# Esquematico_DIY_2.net
KiCad netlist of a schematic drawn in Altium Designer
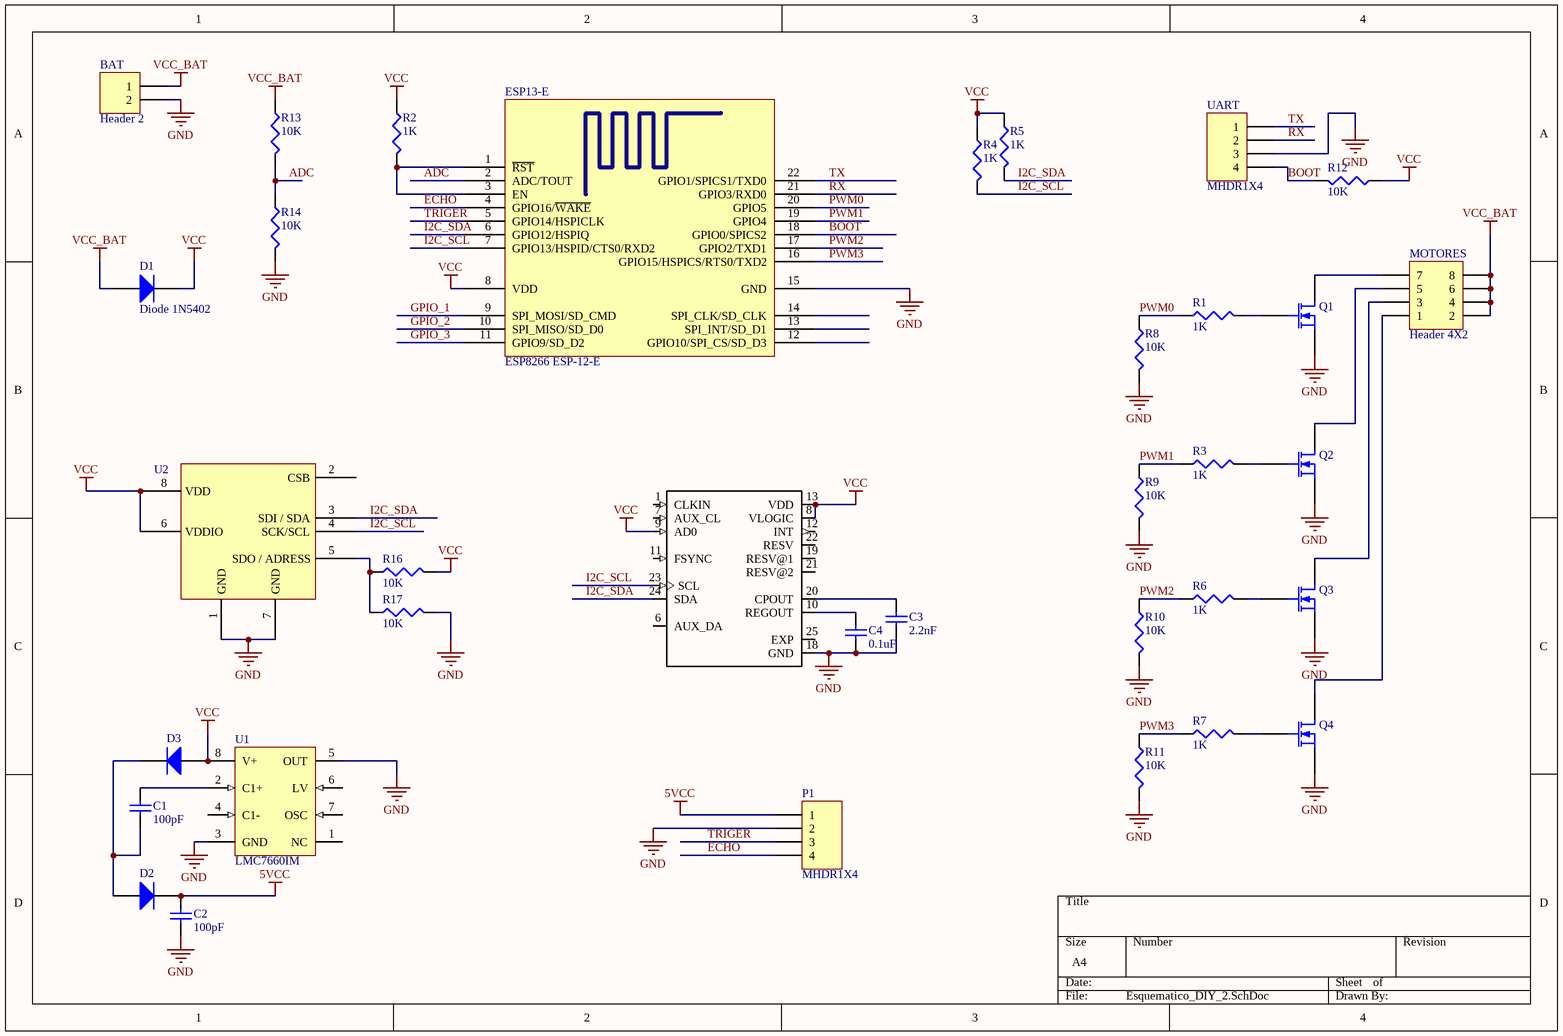
[diagram p0: Esquematico_DIY_2.SchDoc]

(export (version "E")
  (design (tool "Eeschema 10.0.6"))
  (components
    (comp (ref "BAT")
      (value "Header 2")
      (footprint "Miscellaneous Connectors:MHDR1X2")
      (description "Header, 2-Pin")
      (fields (field (name "PUBLISHER") "Altium Limited"))
      (libsource (lib "Miscellaneous Connectors") (part "Header 2"))
    )
    (comp (ref "C1")
      (value "100pF")
      (footprint "Miscellaneous Devices:C0805")
      (description "Capacitor")
      (fields (field (name "Comment") "Cap") (field (name "PUBLISHER") "Altium Limited"))
      (libsource (lib "Miscellaneous Devices") (part "Cap"))
    )
    (comp (ref "C2")
      (value "100pF")
      (footprint "Miscellaneous Devices:C0805")
      (description "Capacitor")
      (fields (field (name "Comment") "Cap") (field (name "PUBLISHER") "Altium Limited"))
      (libsource (lib "Miscellaneous Devices") (part "Cap"))
    )
    (comp (ref "C3")
      (value "2.2nF")
      (footprint "Miscellaneous Devices:C0805")
      (description "Capacitor")
      (fields (field (name "Comment") "Cap") (field (name "PUBLISHER") "Altium Limited"))
      (libsource (lib "Miscellaneous Devices") (part "Cap"))
    )
    (comp (ref "C4")
      (value "0.1uF")
      (footprint "Miscellaneous Devices:C0805")
      (description "Capacitor")
      (fields (field (name "Comment") "Cap") (field (name "PUBLISHER") "Altium Limited"))
      (libsource (lib "Miscellaneous Devices") (part "Cap"))
    )
    (comp (ref "D1")
      (value "Diode 1N5402")
      (footprint "DSO-C2/X2.3")
      (description "3 Amp General Purpose Rectifier")
      (fields (field (name "PUBLISHER") "Altium Limited"))
      (libsource (lib "Miscellaneous Devices") (part "Diode 1N5402"))
    )
    (comp (ref "D2")
      (value "Diode 1N5402")
      (footprint "DSO-C2/Z6.7")
      (description "3 Amp General Purpose Rectifier")
      (fields (field (name "PUBLISHER") "Altium Limited"))
      (libsource (lib "Miscellaneous Devices") (part "Diode 1N5402"))
    )
    (comp (ref "D3")
      (value "Diode 1N5402")
      (footprint "DSO-C2/Z6.7")
      (description "3 Amp General Purpose Rectifier")
      (fields (field (name "PUBLISHER") "Altium Limited"))
      (libsource (lib "Miscellaneous Devices") (part "Diode 1N5402"))
    )
    (comp (ref "ESP13-E")
      (value "ESP8266 ESP-12-E")
      (footprint "ESP8266:ESP8266 ESP-12-E B")
      (libsource (lib "ESP8266") (part "ESP8266 ESP-12-E"))
    )
    (comp (ref "MOTORES")
      (value "Header 4X2")
      (footprint "HDR2X4")
      (description "Header, 4-Pin, Dual row")
      (fields (field (name "PUBLISHER") "Altium Limited"))
      (libsource (lib "Miscellaneous Connectors") (part "Header 4X2"))
    )
    (comp (ref "P1")
      (value "MHDR1X4")
      (footprint "MHDR1X4")
      (description "Header, 4-Pin")
      (fields (field (name "PUBLISHER") "Altium Limited"))
      (libsource (lib "") (part "MHDR1X4_1"))
    )
    (comp (ref "Q1")
      (value "MOSFET-N")
      (footprint "PBL - SMD Packages:SOT23-3")
      (description "N-Channel MOSFET")
      (fields (field (name "PUBLISHER") "Altium Limited"))
      (libsource (lib "Miscellaneous Devices") (part "MOSFET-N"))
    )
    (comp (ref "Q2")
      (value "MOSFET-N")
      (footprint "PBL - SMD Packages:SOT23-3")
      (description "N-Channel MOSFET")
      (fields (field (name "PUBLISHER") "Altium Limited"))
      (libsource (lib "Miscellaneous Devices") (part "MOSFET-N"))
    )
    (comp (ref "Q3")
      (value "MOSFET-N")
      (footprint "PBL - SMD Packages:SOT23-3")
      (description "N-Channel MOSFET")
      (fields (field (name "PUBLISHER") "Altium Limited"))
      (libsource (lib "Miscellaneous Devices") (part "MOSFET-N"))
    )
    (comp (ref "Q4")
      (value "MOSFET-N")
      (footprint "PBL - SMD Packages:SOT23-3")
      (description "N-Channel MOSFET")
      (fields (field (name "PUBLISHER") "Altium Limited"))
      (libsource (lib "Miscellaneous Devices") (part "MOSFET-N"))
    )
    (comp (ref "R1")
      (value "1K")
      (footprint "C0805")
      (description "Resistor")
      (fields (field (name "Comment") "Res3") (field (name "PUBLISHER") "Altium Limited"))
      (libsource (lib "Miscellaneous Devices") (part "Res3"))
    )
    (comp (ref "R2")
      (value "1K")
      (footprint "C0805")
      (description "Resistor")
      (fields (field (name "Comment") "Res3") (field (name "PUBLISHER") "Altium Limited"))
      (libsource (lib "Miscellaneous Devices") (part "Res3"))
    )
    (comp (ref "R3")
      (value "1K")
      (footprint "C0805")
      (description "Resistor")
      (fields (field (name "Comment") "Res3") (field (name "PUBLISHER") "Altium Limited"))
      (libsource (lib "Miscellaneous Devices") (part "Res3"))
    )
    (comp (ref "R4")
      (value "1K")
      (footprint "C1206")
      (description "Resistor")
      (fields (field (name "Comment") "Res3") (field (name "PUBLISHER") "Altium Limited"))
      (libsource (lib "Miscellaneous Devices") (part "Res3"))
    )
    (comp (ref "R5")
      (value "1K")
      (footprint "C1206")
      (description "Resistor")
      (fields (field (name "Comment") "Res3") (field (name "PUBLISHER") "Altium Limited"))
      (libsource (lib "Miscellaneous Devices") (part "Res3"))
    )
    (comp (ref "R6")
      (value "1K")
      (footprint "C0805")
      (description "Resistor")
      (fields (field (name "Comment") "Res3") (field (name "PUBLISHER") "Altium Limited"))
      (libsource (lib "Miscellaneous Devices") (part "Res3"))
    )
    (comp (ref "R7")
      (value "1K")
      (footprint "C0805")
      (description "Resistor")
      (fields (field (name "Comment") "Res3") (field (name "PUBLISHER") "Altium Limited"))
      (libsource (lib "Miscellaneous Devices") (part "Res3"))
    )
    (comp (ref "R8")
      (value "10K")
      (footprint "C0805")
      (description "Resistor")
      (fields (field (name "Comment") "Res3") (field (name "PUBLISHER") "Altium Limited"))
      (libsource (lib "Miscellaneous Devices") (part "Res3"))
    )
    (comp (ref "R9")
      (value "10K")
      (footprint "C0805")
      (description "Resistor")
      (fields (field (name "Comment") "Res3") (field (name "PUBLISHER") "Altium Limited"))
      (libsource (lib "Miscellaneous Devices") (part "Res3"))
    )
    (comp (ref "R10")
      (value "10K")
      (footprint "C0805")
      (description "Resistor")
      (fields (field (name "Comment") "Res3") (field (name "PUBLISHER") "Altium Limited"))
      (libsource (lib "Miscellaneous Devices") (part "Res3"))
    )
    (comp (ref "R11")
      (value "10K")
      (footprint "C0805")
      (description "Resistor")
      (fields (field (name "Comment") "Res3") (field (name "PUBLISHER") "Altium Limited"))
      (libsource (lib "Miscellaneous Devices") (part "Res3"))
    )
    (comp (ref "R12")
      (value "10K")
      (footprint "C0805")
      (description "Resistor")
      (fields (field (name "Comment") "Res3") (field (name "PUBLISHER") "Altium Limited"))
      (libsource (lib "Miscellaneous Devices") (part "Res3"))
    )
    (comp (ref "R13")
      (value "10K")
      (footprint "C0805")
      (description "Resistor")
      (fields (field (name "Comment") "Res3") (field (name "PUBLISHER") "Altium Limited"))
      (libsource (lib "Miscellaneous Devices") (part "Res3"))
    )
    (comp (ref "R14")
      (value "10K")
      (footprint "C0805")
      (description "Resistor")
      (fields (field (name "Comment") "Res3") (field (name "PUBLISHER") "Altium Limited"))
      (libsource (lib "Miscellaneous Devices") (part "Res3"))
    )
    (comp (ref "R16")
      (value "10K")
      (footprint "C0805")
      (description "Resistor")
      (fields (field (name "Comment") "Res3") (field (name "PUBLISHER") "Altium Limited"))
      (libsource (lib "Miscellaneous Devices") (part "Res3"))
    )
    (comp (ref "R17")
      (value "10K")
      (footprint "C1206")
      (description "Resistor")
      (fields (field (name "Comment") "Res3") (field (name "PUBLISHER") "Altium Limited"))
      (libsource (lib "Miscellaneous Devices") (part "Res3"))
    )
    (comp (ref "U1")
      (value "LMC7660IM")
      (footprint "M08A_N")
      (description "Switched Capacitor Voltage Converter, 8-pin Narrow SOIC")
      (fields
        (field (name "MANUFACTURER") "National Semiconductor")
        (field (name "PUBLISHER") "Altium Limited")
      )
      (libsource (lib "NSC Switch Caps") (part "LMC7660IM"))
    )
    (comp (ref "U2")
      (value "BMP280")
      (footprint "LGA-8_BMP280(Primary)")
      (description "Barometro")
      (libsource (lib "BMP280") (part "BMP280"))
    )
    (comp (ref "U3")
      (value "MPU-6050")
      (footprint "QFN50P400X400X95-25N")
      (libsource (lib "MPU-6050") (part "MPU-6050"))
    )
    (comp (ref "UART")
      (value "MHDR1X4")
      (footprint "MHDR1X4")
      (description "Header, 4-Pin")
      (fields (field (name "PUBLISHER") "Altium Limited"))
      (libsource (lib "Miscellaneous Connectors") (part "MHDR1X4"))
    )
  )
  (nets
    (net (code "1") (name "/ADC") (class "Default")
      (node (ref "ESP13-E") (pin "2") (pinfunction "ADC/TOUT_2") (pintype "passive"))
      (node (ref "R13") (pin "2") (pinfunction "2_2") (pintype "passive"))
      (node (ref "R14") (pin "1") (pinfunction "1_1") (pintype "passive"))
    )
    (net (code "2") (name "/BOOT") (class "Default")
      (node (ref "ESP13-E") (pin "18") (pinfunction "GPIO0/SPICS2_18") (pintype "passive"))
      (node (ref "R12") (pin "2") (pinfunction "2_2") (pintype "passive"))
      (node (ref "UART") (pin "4") (pinfunction "4_4") (pintype "passive"))
    )
    (net (code "3") (name "/ECHO") (class "Default")
      (node (ref "ESP13-E") (pin "4") (pinfunction "GPIO16/~{WAKE}_4") (pintype "passive"))
      (node (ref "P1") (pin "4") (pinfunction "4_4") (pintype "passive"))
    )
    (net (code "4") (name "/GPIO_1") (class "Default")
      (node (ref "ESP13-E") (pin "9") (pinfunction "SPI_MOSI/SD_CMD_9") (pintype "passive"))
    )
    (net (code "5") (name "/GPIO_2") (class "Default")
      (node (ref "ESP13-E") (pin "10") (pinfunction "SPI_MISO/SD_D0_10") (pintype "passive"))
    )
    (net (code "6") (name "/GPIO_3") (class "Default")
      (node (ref "ESP13-E") (pin "11") (pinfunction "GPIO9/SD_D2_11") (pintype "passive"))
    )
    (net (code "7") (name "/I2C_SCL") (class "Default")
      (node (ref "ESP13-E") (pin "7") (pinfunction "GPIO13/HSPID/CTS0/RXD2_7") (pintype "passive"))
      (node (ref "R4") (pin "1") (pinfunction "1_1") (pintype "passive"))
      (node (ref "U2") (pin "4") (pinfunction "SCK/SCL_4") (pintype "passive"))
      (node (ref "U3") (pin "23") (pinfunction "SCL_23") (pintype "input"))
    )
    (net (code "8") (name "/I2C_SDA") (class "Default")
      (node (ref "ESP13-E") (pin "6") (pinfunction "GPIO12/HSPIQ_6") (pintype "passive"))
      (node (ref "R5") (pin "1") (pinfunction "1_1") (pintype "passive"))
      (node (ref "U2") (pin "3") (pinfunction "SDI_/_SDA_3") (pintype "passive"))
      (node (ref "U3") (pin "24") (pinfunction "SDA_24") (pintype "bidirectional"))
    )
    (net (code "9") (name "/PWM0") (class "Default")
      (node (ref "ESP13-E") (pin "20") (pinfunction "GPIO5_20") (pintype "passive"))
      (node (ref "R1") (pin "1") (pinfunction "1_1") (pintype "passive"))
      (node (ref "R8") (pin "1") (pinfunction "1_1") (pintype "passive"))
    )
    (net (code "10") (name "/PWM1") (class "Default")
      (node (ref "ESP13-E") (pin "19") (pinfunction "GPIO4_19") (pintype "passive"))
      (node (ref "R3") (pin "1") (pinfunction "1_1") (pintype "passive"))
      (node (ref "R9") (pin "1") (pinfunction "1_1") (pintype "passive"))
    )
    (net (code "11") (name "/PWM2") (class "Default")
      (node (ref "ESP13-E") (pin "17") (pinfunction "GPIO2/TXD1_17") (pintype "passive"))
      (node (ref "R10") (pin "1") (pinfunction "1_1") (pintype "passive"))
      (node (ref "R6") (pin "1") (pinfunction "1_1") (pintype "passive"))
    )
    (net (code "12") (name "/PWM3") (class "Default")
      (node (ref "ESP13-E") (pin "16") (pinfunction "GPIO15/HSPICS/RTS0/TXD2_16") (pintype "passive"))
      (node (ref "R11") (pin "1") (pinfunction "1_1") (pintype "passive"))
      (node (ref "R7") (pin "1") (pinfunction "1_1") (pintype "passive"))
    )
    (net (code "13") (name "/RX") (class "Default")
      (node (ref "ESP13-E") (pin "21") (pinfunction "GPIO3/RXD0_21") (pintype "passive"))
      (node (ref "UART") (pin "2") (pinfunction "2_2") (pintype "passive"))
    )
    (net (code "14") (name "/TRIGER") (class "Default")
      (node (ref "ESP13-E") (pin "5") (pinfunction "GPIO14/HSPICLK_5") (pintype "passive"))
      (node (ref "P1") (pin "3") (pinfunction "3_3") (pintype "passive"))
    )
    (net (code "15") (name "/TX") (class "Default")
      (node (ref "ESP13-E") (pin "22") (pinfunction "GPIO1/SPICS1/TXD0_22") (pintype "passive"))
      (node (ref "UART") (pin "1") (pinfunction "1_1") (pintype "passive"))
    )
    (net (code "16") (name "5VCC") (class "Default")
      (node (ref "C2") (pin "2") (pinfunction "2_2") (pintype "passive"))
      (node (ref "D2") (pin "2") (pinfunction "K_2") (pintype "passive"))
      (node (ref "P1") (pin "1") (pinfunction "1_1") (pintype "passive"))
    )
    (net (code "17") (name "GND") (class "Default")
      (node (ref "BAT") (pin "2") (pinfunction "2_2") (pintype "passive"))
      (node (ref "C2") (pin "1") (pinfunction "1_1") (pintype "passive"))
      (node (ref "C3") (pin "2") (pinfunction "2_2") (pintype "passive"))
      (node (ref "C4") (pin "2") (pinfunction "2_2") (pintype "passive"))
      (node (ref "ESP13-E") (pin "15") (pinfunction "GND_15") (pintype "passive"))
      (node (ref "P1") (pin "2") (pinfunction "2_2") (pintype "passive"))
      (node (ref "Q1") (pin "3") (pinfunction "S_3") (pintype "passive"))
      (node (ref "Q2") (pin "3") (pinfunction "S_3") (pintype "passive"))
      (node (ref "Q3") (pin "3") (pinfunction "S_3") (pintype "passive"))
      (node (ref "Q4") (pin "3") (pinfunction "S_3") (pintype "passive"))
      (node (ref "R10") (pin "2") (pinfunction "2_2") (pintype "passive"))
      (node (ref "R11") (pin "2") (pinfunction "2_2") (pintype "passive"))
      (node (ref "R14") (pin "2") (pinfunction "2_2") (pintype "passive"))
      (node (ref "R17") (pin "2") (pinfunction "2_2") (pintype "passive"))
      (node (ref "R8") (pin "2") (pinfunction "2_2") (pintype "passive"))
      (node (ref "R9") (pin "2") (pinfunction "2_2") (pintype "passive"))
      (node (ref "U1") (pin "3") (pinfunction "GND_3") (pintype "power_in"))
      (node (ref "U1") (pin "5") (pinfunction "OUT_5") (pintype "power_in"))
      (node (ref "U2") (pin "1") (pinfunction "GND_1") (pintype "passive"))
      (node (ref "U2") (pin "7") (pinfunction "GND_7") (pintype "passive"))
      (node (ref "U3") (pin "18") (pinfunction "GND_18") (pintype "power_in"))
      (node (ref "UART") (pin "3") (pinfunction "3_3") (pintype "passive"))
    )
    (net (code "18") (name "Net-(D2-A)") (class "Default")
      (node (ref "C1") (pin "2") (pinfunction "2_2") (pintype "passive"))
      (node (ref "D2") (pin "1") (pinfunction "A_1") (pintype "passive"))
      (node (ref "D3") (pin "2") (pinfunction "K_2") (pintype "passive"))
    )
    (net (code "19") (name "Net-(ESP13-E-EN)") (class "Default")
      (node (ref "ESP13-E") (pin "1") (pinfunction "~{RST}_1") (pintype "passive"))
      (node (ref "ESP13-E") (pin "3") (pinfunction "EN_3") (pintype "passive"))
      (node (ref "R2") (pin "2") (pinfunction "2_2") (pintype "passive"))
    )
    (net (code "20") (name "Net-(Q1-D)") (class "Default")
      (node (ref "MOTORES") (pin "7") (pinfunction "7_7") (pintype "passive"))
      (node (ref "Q1") (pin "1") (pinfunction "D_1") (pintype "passive"))
    )
    (net (code "21") (name "Net-(Q1-G)") (class "Default")
      (node (ref "Q1") (pin "2") (pinfunction "G_2") (pintype "passive"))
      (node (ref "R1") (pin "2") (pinfunction "2_2") (pintype "passive"))
    )
    (net (code "22") (name "Net-(Q2-D)") (class "Default")
      (node (ref "MOTORES") (pin "5") (pinfunction "5_5") (pintype "passive"))
      (node (ref "Q2") (pin "1") (pinfunction "D_1") (pintype "passive"))
    )
    (net (code "23") (name "Net-(Q2-G)") (class "Default")
      (node (ref "Q2") (pin "2") (pinfunction "G_2") (pintype "passive"))
      (node (ref "R3") (pin "2") (pinfunction "2_2") (pintype "passive"))
    )
    (net (code "24") (name "Net-(Q3-D)") (class "Default")
      (node (ref "MOTORES") (pin "3") (pinfunction "3_3") (pintype "passive"))
      (node (ref "Q3") (pin "1") (pinfunction "D_1") (pintype "passive"))
    )
    (net (code "25") (name "Net-(Q3-G)") (class "Default")
      (node (ref "Q3") (pin "2") (pinfunction "G_2") (pintype "passive"))
      (node (ref "R6") (pin "2") (pinfunction "2_2") (pintype "passive"))
    )
    (net (code "26") (name "Net-(Q4-D)") (class "Default")
      (node (ref "MOTORES") (pin "1") (pinfunction "1_1") (pintype "passive"))
      (node (ref "Q4") (pin "1") (pinfunction "D_1") (pintype "passive"))
    )
    (net (code "27") (name "Net-(Q4-G)") (class "Default")
      (node (ref "Q4") (pin "2") (pinfunction "G_2") (pintype "passive"))
      (node (ref "R7") (pin "2") (pinfunction "2_2") (pintype "passive"))
    )
    (net (code "28") (name "Net-(U1-C1+)") (class "Default")
      (node (ref "C1") (pin "1") (pinfunction "1_1") (pintype "passive"))
      (node (ref "U1") (pin "2") (pinfunction "C1+_2") (pintype "input"))
    )
    (net (code "29") (name "Net-(U2-SDO_{slash}_ADRESS)") (class "Default")
      (node (ref "R16") (pin "1") (pinfunction "1_1") (pintype "passive"))
      (node (ref "R17") (pin "1") (pinfunction "1_1") (pintype "passive"))
      (node (ref "U2") (pin "5") (pinfunction "SDO_/_ADRESS_5") (pintype "passive"))
    )
    (net (code "30") (name "Net-(U3-CPOUT)") (class "Default")
      (node (ref "C3") (pin "1") (pinfunction "1_1") (pintype "passive"))
      (node (ref "U3") (pin "20") (pinfunction "CPOUT_20") (pintype "passive"))
    )
    (net (code "31") (name "Net-(U3-REGOUT)") (class "Default")
      (node (ref "C4") (pin "1") (pinfunction "1_1") (pintype "passive"))
      (node (ref "U3") (pin "10") (pinfunction "REGOUT_10") (pintype "passive"))
    )
    (net (code "32") (name "VCC") (class "Default")
      (node (ref "D1") (pin "2") (pinfunction "K_2") (pintype "passive"))
      (node (ref "D3") (pin "1") (pinfunction "A_1") (pintype "passive"))
      (node (ref "ESP13-E") (pin "8") (pinfunction "VDD_8") (pintype "passive"))
      (node (ref "R12") (pin "1") (pinfunction "1_1") (pintype "passive"))
      (node (ref "R16") (pin "2") (pinfunction "2_2") (pintype "passive"))
      (node (ref "R2") (pin "1") (pinfunction "1_1") (pintype "passive"))
      (node (ref "R4") (pin "2") (pinfunction "2_2") (pintype "passive"))
      (node (ref "R5") (pin "2") (pinfunction "2_2") (pintype "passive"))
      (node (ref "U1") (pin "8") (pinfunction "V+_8") (pintype "power_in"))
      (node (ref "U2") (pin "6") (pinfunction "VDDIO_6") (pintype "passive"))
      (node (ref "U2") (pin "8") (pinfunction "VDD_8") (pintype "passive"))
      (node (ref "U3") (pin "13") (pinfunction "VDD_13") (pintype "power_in"))
      (node (ref "U3") (pin "8") (pinfunction "VLOGIC_8") (pintype "power_in"))
      (node (ref "U3") (pin "9") (pinfunction "AD0_9") (pintype "input"))
    )
    (net (code "33") (name "VCC_BAT") (class "Default")
      (node (ref "BAT") (pin "1") (pinfunction "1_1") (pintype "passive"))
      (node (ref "D1") (pin "1") (pinfunction "A_1") (pintype "passive"))
      (node (ref "MOTORES") (pin "2") (pinfunction "2_2") (pintype "passive"))
      (node (ref "MOTORES") (pin "4") (pinfunction "4_4") (pintype "passive"))
      (node (ref "MOTORES") (pin "6") (pinfunction "6_6") (pintype "passive"))
      (node (ref "MOTORES") (pin "8") (pinfunction "8_8") (pintype "passive"))
      (node (ref "R13") (pin "1") (pinfunction "1_1") (pintype "passive"))
    )
    (net (code "34") (name "unconnected-(ESP13-E-GPIO10{slash}SPI_CS{slash}SD_D3-Pad12)") (class "Default")
      (node (ref "ESP13-E") (pin "12") (pinfunction "GPIO10/SPI_CS/SD_D3_12") (pintype "passive"))
    )
    (net (code "35") (name "unconnected-(ESP13-E-SPI_CLK{slash}SD_CLK-Pad14)") (class "Default")
      (node (ref "ESP13-E") (pin "14") (pinfunction "SPI_CLK/SD_CLK_14") (pintype "passive"))
    )
    (net (code "36") (name "unconnected-(ESP13-E-SPI_INT{slash}SD_D1-Pad13)") (class "Default")
      (node (ref "ESP13-E") (pin "13") (pinfunction "SPI_INT/SD_D1_13") (pintype "passive"))
    )
    (net (code "37") (name "unconnected-(U1-C1--Pad4)") (class "Default")
      (node (ref "U1") (pin "4") (pinfunction "C1-_4") (pintype "input"))
    )
    (net (code "38") (name "unconnected-(U1-LV-Pad6)") (class "Default")
      (node (ref "U1") (pin "6") (pinfunction "LV_6") (pintype "input"))
    )
    (net (code "39") (name "unconnected-(U1-NC-Pad1)") (class "Default")
      (node (ref "U1") (pin "1") (pinfunction "NC_1") (pintype "passive"))
    )
    (net (code "40") (name "unconnected-(U1-OSC-Pad7)") (class "Default")
      (node (ref "U1") (pin "7") (pinfunction "OSC_7") (pintype "input"))
    )
    (net (code "41") (name "unconnected-(U2-CSB-Pad2)") (class "Default")
      (node (ref "U2") (pin "2") (pinfunction "CSB_2") (pintype "passive"))
    )
    (net (code "42") (name "unconnected-(U3-AUX_CL-Pad7)") (class "Default")
      (node (ref "U3") (pin "7") (pinfunction "AUX_CL_7") (pintype "input"))
    )
    (net (code "43") (name "unconnected-(U3-AUX_DA-Pad6)") (class "Default")
      (node (ref "U3") (pin "6") (pinfunction "AUX_DA_6") (pintype "bidirectional"))
    )
    (net (code "44") (name "unconnected-(U3-CLKIN-Pad1)") (class "Default")
      (node (ref "U3") (pin "1") (pinfunction "CLKIN_1") (pintype "input"))
    )
    (net (code "45") (name "unconnected-(U3-EXP-Pad25)") (class "Default")
      (node (ref "U3") (pin "25") (pinfunction "EXP_25") (pintype "power_in"))
    )
    (net (code "46") (name "unconnected-(U3-FSYNC-Pad11)") (class "Default")
      (node (ref "U3") (pin "11") (pinfunction "FSYNC_11") (pintype "input"))
    )
    (net (code "47") (name "unconnected-(U3-INT-Pad12)") (class "Default")
      (node (ref "U3") (pin "12") (pinfunction "INT_12") (pintype "output"))
    )
    (net (code "48") (name "unconnected-(U3-RESV-Pad22)") (class "Default")
      (node (ref "U3") (pin "22") (pinfunction "RESV_22") (pintype "passive"))
    )
    (net (code "49") (name "unconnected-(U3-RESV@1-Pad19)") (class "Default")
      (node (ref "U3") (pin "19") (pinfunction "RESV@1_19") (pintype "passive"))
    )
    (net (code "50") (name "unconnected-(U3-RESV@2-Pad21)") (class "Default")
      (node (ref "U3") (pin "21") (pinfunction "RESV@2_21") (pintype "passive"))
    )
  )
)
